# MicroMultimeter_PWR_Sch.net
KiCad netlist of a schematic drawn in Altium Designer
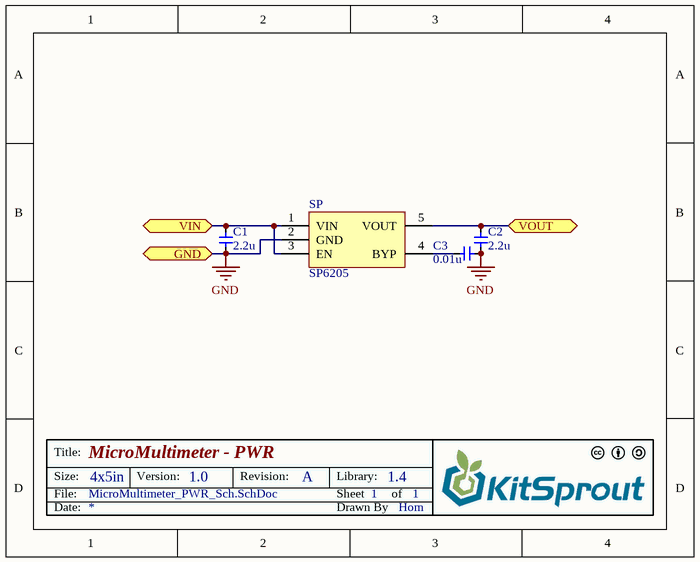
[diagram p0: MicroMultimeter_PWR_Sch.SchDoc]

(export (version "E")
  (design (tool "Eeschema 10.0.6"))
  (components
    (comp (ref "C1")
      (value "2.2u")
      (footprint "CAP_0603")
      (description "Capacitor")
      (fields (field (name "Comment") "Cap_0603"))
      (libsource (lib "SCH_Passive") (part "Cap_0603"))
    )
    (comp (ref "C2")
      (value "2.2u")
      (footprint "CAP_0603")
      (description "Capacitor")
      (fields (field (name "Comment") "Cap_0603"))
      (libsource (lib "SCH_Passive") (part "Cap_0603"))
    )
    (comp (ref "C3")
      (value "0.01u")
      (footprint "CAP_0603")
      (description "Capacitor")
      (fields (field (name "Comment") "Cap_0603"))
      (libsource (lib "SCH_Passive") (part "Cap_0603"))
    )
    (comp (ref "SP")
      (value "SP6205")
      (footprint "PCB_IntegratedCircuit:SOT23-5")
      (description "Power")
      (libsource (lib "SCH_IntegratedCircuit") (part "SP6205"))
    )
  )
  (nets
    (net (code "1") (name "/VIN") (class "Default")
      (node (ref "C1") (pin "2") (pinfunction "2_2") (pintype "passive"))
      (node (ref "SP") (pin "1") (pinfunction "VIN_1") (pintype "passive"))
      (node (ref "SP") (pin "3") (pinfunction "EN_3") (pintype "power_in"))
    )
    (net (code "2") (name "/VOUT") (class "Default")
      (node (ref "C2") (pin "2") (pinfunction "2_2") (pintype "passive"))
      (node (ref "SP") (pin "5") (pinfunction "VOUT_5") (pintype "passive"))
    )
    (net (code "3") (name "GND") (class "Default")
      (node (ref "C1") (pin "1") (pinfunction "1_1") (pintype "passive"))
      (node (ref "C2") (pin "1") (pinfunction "1_1") (pintype "passive"))
      (node (ref "C3") (pin "1") (pinfunction "1_1") (pintype "passive"))
      (node (ref "SP") (pin "2") (pinfunction "GND_2") (pintype "passive"))
    )
    (net (code "4") (name "Net-(SP-BYP)") (class "Default")
      (node (ref "C3") (pin "2") (pinfunction "2_2") (pintype "passive"))
      (node (ref "SP") (pin "4") (pinfunction "BYP_4") (pintype "passive"))
    )
  )
)
